# I2C_Bus_Multiplexer.net
KiCad netlist of a schematic drawn in Altium Designer
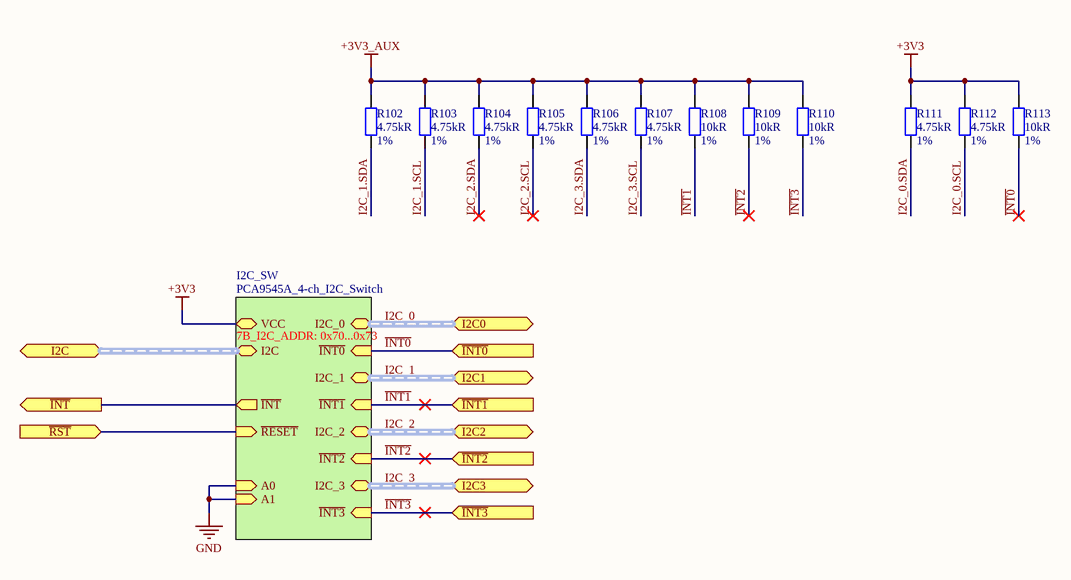
[diagram p0: I2C_Bus_Multiplexer.SchDoc]

(export (version "E")
  (design (tool "Eeschema 10.0.6"))
  (components
    (comp (ref "R102")
      (value "RES SMD 4.75K OHM 1% 1/16W 0402")
      (footprint "R0402")
      (description "4.75 kOhms ±1% 0.063W, 1/16W Chip Resistor 0402 (1005 Metric) Moisture Resistant Thick Film")
      (fields
        (field (name "MANUFACTURER") "Yageo")
        (field (name "MANUFACTURER PART NUMBER") "RC0402FR-074K75P")
        (field (name "RESISTANCE") "4.75kR")
        (field (name "TOLERANCE") "1%")
      )
      (libsource (lib "resistors_smd") (part "RES SMD 4.75K OHM 1% 1/16W 0402"))
    )
    (comp (ref "R103")
      (value "RES SMD 4.75K OHM 1% 1/16W 0402")
      (footprint "R0402")
      (description "4.75 kOhms ±1% 0.063W, 1/16W Chip Resistor 0402 (1005 Metric) Moisture Resistant Thick Film")
      (fields
        (field (name "MANUFACTURER") "Yageo")
        (field (name "MANUFACTURER PART NUMBER") "RC0402FR-074K75P")
        (field (name "RESISTANCE") "4.75kR")
        (field (name "TOLERANCE") "1%")
      )
      (libsource (lib "resistors_smd") (part "RES SMD 4.75K OHM 1% 1/16W 0402"))
    )
    (comp (ref "R104")
      (value "RES SMD 4.75K OHM 1% 1/16W 0402")
      (footprint "R0402")
      (description "4.75 kOhms ±1% 0.063W, 1/16W Chip Resistor 0402 (1005 Metric) Moisture Resistant Thick Film")
      (fields
        (field (name "MANUFACTURER") "Yageo")
        (field (name "MANUFACTURER PART NUMBER") "RC0402FR-074K75P")
        (field (name "RESISTANCE") "4.75kR")
        (field (name "TOLERANCE") "1%")
      )
      (libsource (lib "resistors_smd") (part "RES SMD 4.75K OHM 1% 1/16W 0402"))
    )
    (comp (ref "R105")
      (value "RES SMD 4.75K OHM 1% 1/16W 0402")
      (footprint "R0402")
      (description "4.75 kOhms ±1% 0.063W, 1/16W Chip Resistor 0402 (1005 Metric) Moisture Resistant Thick Film")
      (fields
        (field (name "MANUFACTURER") "Yageo")
        (field (name "MANUFACTURER PART NUMBER") "RC0402FR-074K75P")
        (field (name "RESISTANCE") "4.75kR")
        (field (name "TOLERANCE") "1%")
      )
      (libsource (lib "resistors_smd") (part "RES SMD 4.75K OHM 1% 1/16W 0402"))
    )
    (comp (ref "R106")
      (value "RES SMD 4.75K OHM 1% 1/16W 0402")
      (footprint "R0402")
      (description "4.75 kOhms ±1% 0.063W, 1/16W Chip Resistor 0402 (1005 Metric) Moisture Resistant Thick Film")
      (fields
        (field (name "MANUFACTURER") "Yageo")
        (field (name "MANUFACTURER PART NUMBER") "RC0402FR-074K75P")
        (field (name "RESISTANCE") "4.75kR")
        (field (name "TOLERANCE") "1%")
      )
      (libsource (lib "resistors_smd") (part "RES SMD 4.75K OHM 1% 1/16W 0402"))
    )
    (comp (ref "R107")
      (value "RES SMD 4.75K OHM 1% 1/16W 0402")
      (footprint "R0402")
      (description "4.75 kOhms ±1% 0.063W, 1/16W Chip Resistor 0402 (1005 Metric) Moisture Resistant Thick Film")
      (fields
        (field (name "MANUFACTURER") "Yageo")
        (field (name "MANUFACTURER PART NUMBER") "RC0402FR-074K75P")
        (field (name "RESISTANCE") "4.75kR")
        (field (name "TOLERANCE") "1%")
      )
      (libsource (lib "resistors_smd") (part "RES SMD 4.75K OHM 1% 1/16W 0402"))
    )
    (comp (ref "R108")
      (value "RES SMD 10K OHM 1% 1/16W 0402")
      (footprint "R0402")
      (description "10 kOhms ±1% 0.063W, 1/16W Chip Resistor 0402 (1005 Metric) Moisture Resistant Thick Film")
      (fields
        (field (name "MANUFACTURER") "Yageo")
        (field (name "MANUFACTURER PART NUMBER") "RC0402FR-0710KP")
        (field (name "RESISTANCE") "10kR")
        (field (name "TOLERANCE") "1%")
      )
      (libsource (lib "resistors_smd") (part "RES SMD 10K OHM 1% 1/16W 0402"))
    )
    (comp (ref "R109")
      (value "RES SMD 10K OHM 1% 1/16W 0402")
      (footprint "R0402")
      (description "10 kOhms ±1% 0.063W, 1/16W Chip Resistor 0402 (1005 Metric) Moisture Resistant Thick Film")
      (fields
        (field (name "MANUFACTURER") "Yageo")
        (field (name "MANUFACTURER PART NUMBER") "RC0402FR-0710KP")
        (field (name "RESISTANCE") "10kR")
        (field (name "TOLERANCE") "1%")
      )
      (libsource (lib "resistors_smd") (part "RES SMD 10K OHM 1% 1/16W 0402"))
    )
    (comp (ref "R110")
      (value "RES SMD 10K OHM 1% 1/16W 0402")
      (footprint "R0402")
      (description "10 kOhms ±1% 0.063W, 1/16W Chip Resistor 0402 (1005 Metric) Moisture Resistant Thick Film")
      (fields
        (field (name "MANUFACTURER") "Yageo")
        (field (name "MANUFACTURER PART NUMBER") "RC0402FR-0710KP")
        (field (name "RESISTANCE") "10kR")
        (field (name "TOLERANCE") "1%")
      )
      (libsource (lib "resistors_smd") (part "RES SMD 10K OHM 1% 1/16W 0402"))
    )
    (comp (ref "R111")
      (value "RES SMD 4.75K OHM 1% 1/16W 0402")
      (footprint "R0402")
      (description "4.75 kOhms ±1% 0.063W, 1/16W Chip Resistor 0402 (1005 Metric) Moisture Resistant Thick Film")
      (fields
        (field (name "MANUFACTURER") "Yageo")
        (field (name "MANUFACTURER PART NUMBER") "RC0402FR-074K75P")
        (field (name "RESISTANCE") "4.75kR")
        (field (name "TOLERANCE") "1%")
      )
      (libsource (lib "resistors_smd") (part "RES SMD 4.75K OHM 1% 1/16W 0402"))
    )
    (comp (ref "R112")
      (value "RES SMD 4.75K OHM 1% 1/16W 0402")
      (footprint "R0402")
      (description "4.75 kOhms ±1% 0.063W, 1/16W Chip Resistor 0402 (1005 Metric) Moisture Resistant Thick Film")
      (fields
        (field (name "MANUFACTURER") "Yageo")
        (field (name "MANUFACTURER PART NUMBER") "RC0402FR-074K75P")
        (field (name "RESISTANCE") "4.75kR")
        (field (name "TOLERANCE") "1%")
      )
      (libsource (lib "resistors_smd") (part "RES SMD 4.75K OHM 1% 1/16W 0402"))
    )
    (comp (ref "R113")
      (value "RES SMD 10K OHM 1% 1/16W 0402")
      (footprint "R0402")
      (description "10 kOhms ±1% 0.063W, 1/16W Chip Resistor 0402 (1005 Metric) Moisture Resistant Thick Film")
      (fields
        (field (name "MANUFACTURER") "Yageo")
        (field (name "MANUFACTURER PART NUMBER") "RC0402FR-0710KP")
        (field (name "RESISTANCE") "10kR")
        (field (name "TOLERANCE") "1%")
      )
      (libsource (lib "resistors_smd") (part "RES SMD 10K OHM 1% 1/16W 0402"))
    )
  )
  (nets
    (net (code "6") (name "+3V3") (class "Default")
      (node (ref "R111") (pin "2") (pinfunction "2_2") (pintype "passive"))
      (node (ref "R112") (pin "2") (pinfunction "2_2") (pintype "passive"))
      (node (ref "R113") (pin "1") (pinfunction "1_1") (pintype "passive"))
    )
    (net (code "7") (name "+3V3_AUX") (class "Default")
      (node (ref "R102") (pin "2") (pinfunction "2_2") (pintype "passive"))
      (node (ref "R103") (pin "2") (pinfunction "2_2") (pintype "passive"))
      (node (ref "R104") (pin "2") (pinfunction "2_2") (pintype "passive"))
      (node (ref "R105") (pin "2") (pinfunction "2_2") (pintype "passive"))
      (node (ref "R106") (pin "2") (pinfunction "2_2") (pintype "passive"))
      (node (ref "R107") (pin "2") (pinfunction "2_2") (pintype "passive"))
      (node (ref "R108") (pin "1") (pinfunction "1_1") (pintype "passive"))
      (node (ref "R109") (pin "1") (pinfunction "1_1") (pintype "passive"))
      (node (ref "R110") (pin "1") (pinfunction "1_1") (pintype "passive"))
    )
    (net (code "8") (name "/I2C_0.SCL") (class "Default")
      (node (ref "R112") (pin "1") (pinfunction "1_1") (pintype "passive"))
    )
    (net (code "9") (name "/I2C_0.SDA") (class "Default")
      (node (ref "R111") (pin "1") (pinfunction "1_1") (pintype "passive"))
    )
    (net (code "10") (name "/I2C_1.SCL") (class "Default")
      (node (ref "R103") (pin "1") (pinfunction "1_1") (pintype "passive"))
    )
    (net (code "11") (name "/I2C_1.SDA") (class "Default")
      (node (ref "R102") (pin "1") (pinfunction "1_1") (pintype "passive"))
    )
    (net (code "12") (name "/I2C_2.SCL") (class "Default")
      (node (ref "R105") (pin "1") (pinfunction "1_1") (pintype "passive+no_connect"))
    )
    (net (code "13") (name "/I2C_2.SDA") (class "Default")
      (node (ref "R104") (pin "1") (pinfunction "1_1") (pintype "passive+no_connect"))
    )
    (net (code "14") (name "/I2C_3.SCL") (class "Default")
      (node (ref "R107") (pin "1") (pinfunction "1_1") (pintype "passive"))
    )
    (net (code "15") (name "/I2C_3.SDA") (class "Default")
      (node (ref "R106") (pin "1") (pinfunction "1_1") (pintype "passive"))
    )
    (net (code "18") (name "/INT0") (class "Default")
      (node (ref "R113") (pin "2") (pinfunction "2_2") (pintype "passive"))
    )
    (net (code "19") (name "/INT1") (class "Default")
      (node (ref "R108") (pin "2") (pinfunction "2_2") (pintype "passive"))
    )
    (net (code "20") (name "/INT2") (class "Default")
      (node (ref "R109") (pin "2") (pinfunction "2_2") (pintype "passive"))
    )
    (net (code "21") (name "/INT3") (class "Default")
      (node (ref "R110") (pin "2") (pinfunction "2_2") (pintype "passive"))
    )
  )
)
